# Child.net
KiCad netlist of a schematic drawn in EAGLE
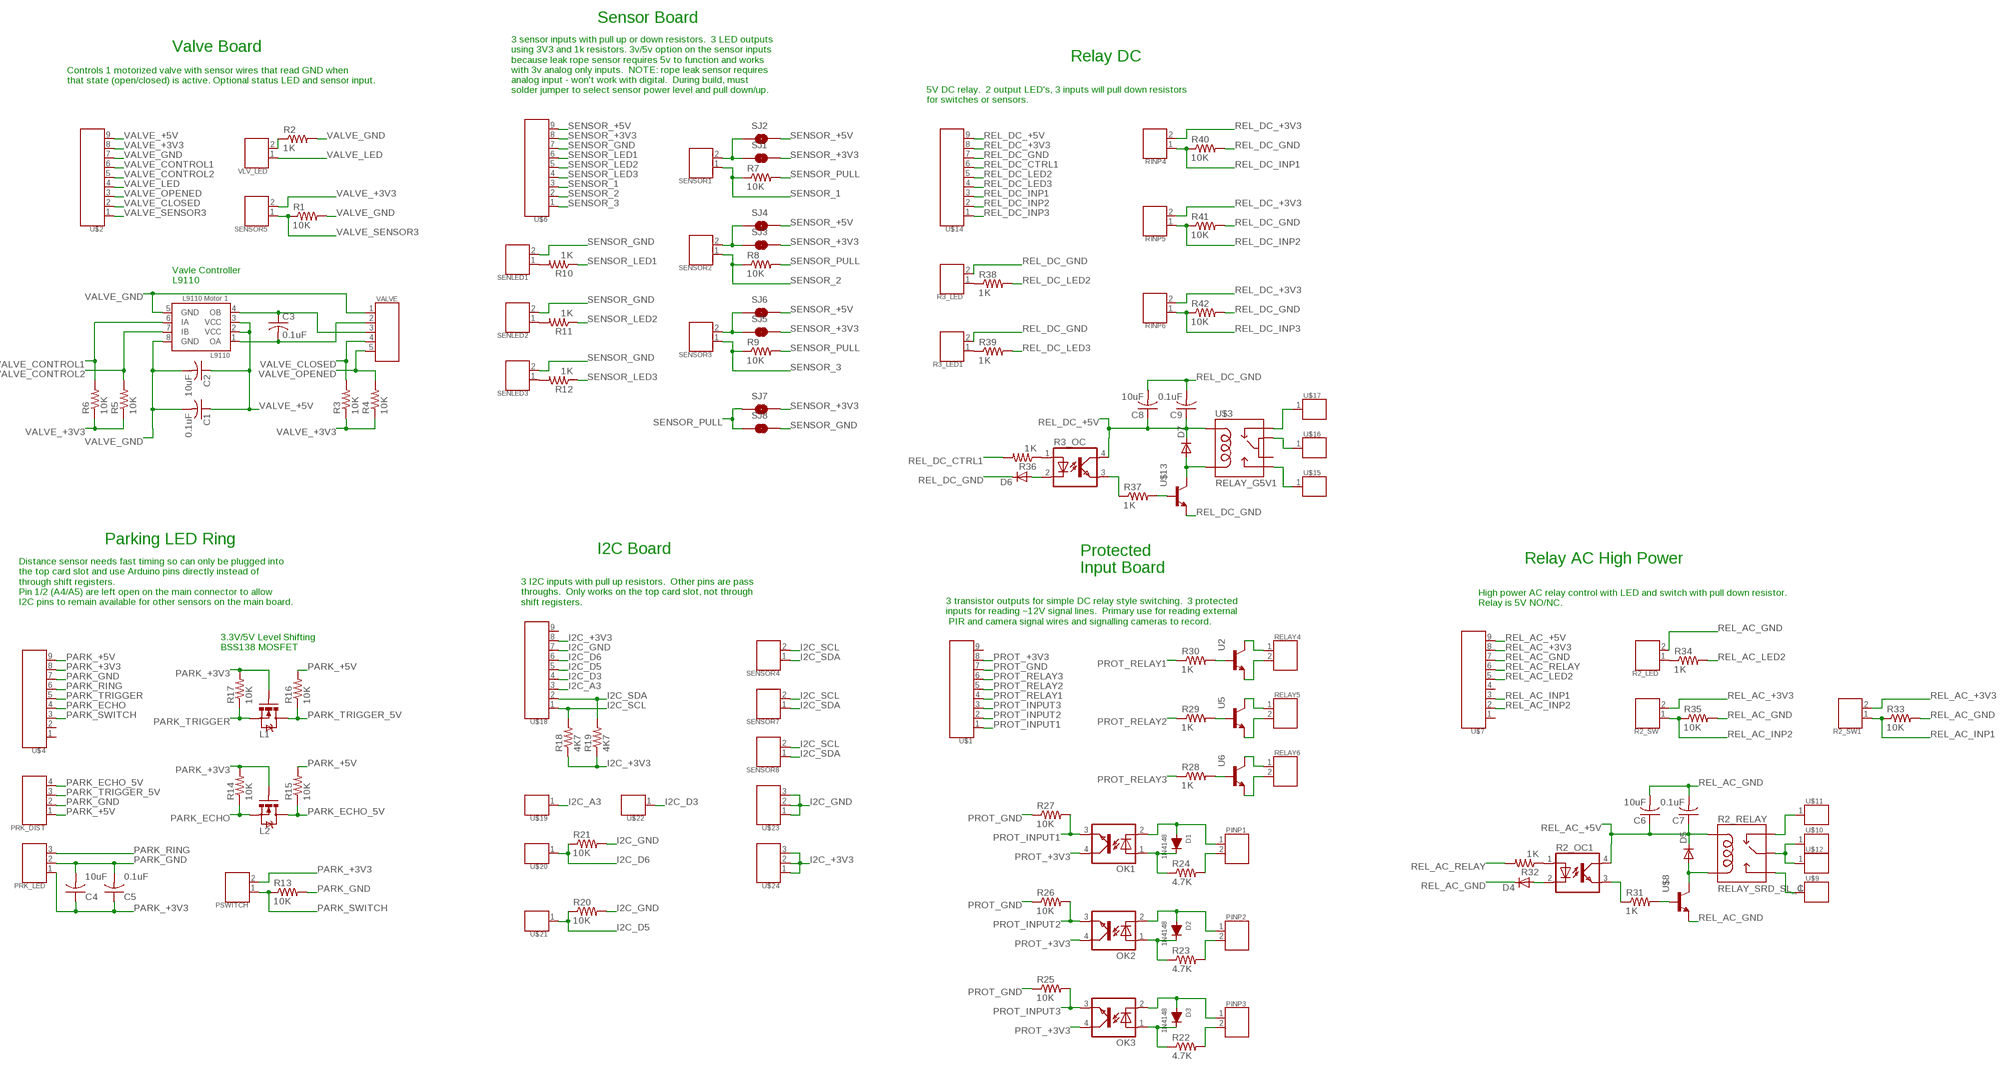
[diagram p0: schematic, sheet 1]

(export (version "E")
  (design (tool "Eeschema 10.0.6"))
  (components
    (comp (ref "C1")
      (value "0.1uF")
      (footprint "eagle-import:CAP_0805")
      (libsource (lib "eagle-import") (part "CAP_0805"))
    )
    (comp (ref "C2")
      (value "10uF")
      (footprint "eagle-import:CAP_0805")
      (libsource (lib "eagle-import") (part "CAP_0805"))
    )
    (comp (ref "C3")
      (value "0.1uF")
      (footprint "eagle-import:CAP_0805")
      (libsource (lib "eagle-import") (part "CAP_0805"))
    )
    (comp (ref "C4")
      (value "10uF")
      (footprint "eagle-import:CAP_0805")
      (libsource (lib "eagle-import") (part "CAP_0805"))
    )
    (comp (ref "C5")
      (value "0.1uF")
      (footprint "eagle-import:CAP_0805")
      (libsource (lib "eagle-import") (part "CAP_0805"))
    )
    (comp (ref "C6")
      (value "10uF")
      (footprint "eagle-import:CAP_0805")
      (libsource (lib "eagle-import") (part "CAP_0805"))
    )
    (comp (ref "C7")
      (value "0.1uF")
      (footprint "eagle-import:CAP_0805")
      (libsource (lib "eagle-import") (part "CAP_0805"))
    )
    (comp (ref "C8")
      (value "10uF")
      (footprint "eagle-import:CAP_0805")
      (libsource (lib "eagle-import") (part "CAP_0805"))
    )
    (comp (ref "C9")
      (value "0.1uF")
      (footprint "eagle-import:CAP_0805")
      (libsource (lib "eagle-import") (part "CAP_0805"))
    )
    (comp (ref "D1")
      (value "1N4148")
      (footprint "eagle-import:SOD123")
      (fields (field (name "MPN") "1N4148W"))
      (libsource (lib "eagle-import") (part "1N4148_SOD123"))
    )
    (comp (ref "D2")
      (value "1N4148")
      (footprint "eagle-import:SOD123")
      (fields (field (name "MPN") "1N4148W"))
      (libsource (lib "eagle-import") (part "1N4148_SOD123"))
    )
    (comp (ref "D3")
      (value "1N4148")
      (footprint "eagle-import:SOD123")
      (fields (field (name "MPN") "1N4148W"))
      (libsource (lib "eagle-import") (part "1N4148_SOD123"))
    )
    (comp (ref "D4")
      (value "DIODESOD323")
      (footprint "eagle-import:SOD323")
      (libsource (lib "eagle-import") (part "DIODESOD323"))
    )
    (comp (ref "D5")
      (value "DIODESOD323")
      (footprint "eagle-import:SOD323")
      (libsource (lib "eagle-import") (part "DIODESOD323"))
    )
    (comp (ref "D6")
      (value "DIODESOD323")
      (footprint "eagle-import:SOD323")
      (libsource (lib "eagle-import") (part "DIODESOD323"))
    )
    (comp (ref "D7")
      (value "DIODESOD323")
      (footprint "eagle-import:SOD323")
      (libsource (lib "eagle-import") (part "DIODESOD323"))
    )
    (comp (ref "L1")
      (value "MOSFET-NCHANNELSMD")
      (footprint "eagle-import:SOT23-3")
      (libsource (lib "eagle-import") (part "MOSFET-NCHANNELSMD"))
    )
    (comp (ref "L2")
      (value "MOSFET-NCHANNELSMD")
      (footprint "eagle-import:SOT23-3")
      (libsource (lib "eagle-import") (part "MOSFET-NCHANNELSMD"))
    )
    (comp (ref "L9110")
      (value "L9110 Motor 1")
      (footprint "eagle-import:SO-08")
      (libsource (lib "eagle-import") (part "IC_L9110_MOTORSO8"))
    )
    (comp (ref "OK1")
      (value "PC817SOP")
      (footprint "eagle-import:SO-4_PC817")
      (libsource (lib "eagle-import") (part "PC817SOP"))
    )
    (comp (ref "OK2")
      (value "PC817SOP")
      (footprint "eagle-import:SO-4_PC817")
      (libsource (lib "eagle-import") (part "PC817SOP"))
    )
    (comp (ref "OK3")
      (value "PC817SOP")
      (footprint "eagle-import:SO-4_PC817")
      (libsource (lib "eagle-import") (part "PC817SOP"))
    )
    (comp (ref "PINP1")
      (value "CONNECTOR_2DUPONT")
      (footprint "eagle-import:DUPONT_2")
      (libsource (lib "eagle-import") (part "CONNECTOR_2DUPONT"))
    )
    (comp (ref "PINP2")
      (value "CONNECTOR_2DUPONT")
      (footprint "eagle-import:DUPONT_2")
      (libsource (lib "eagle-import") (part "CONNECTOR_2DUPONT"))
    )
    (comp (ref "PINP3")
      (value "CONNECTOR_2DUPONT")
      (footprint "eagle-import:DUPONT_2")
      (libsource (lib "eagle-import") (part "CONNECTOR_2DUPONT"))
    )
    (comp (ref "PRK_DIST")
      (value "CONNECTOR_4DUPONT")
      (footprint "eagle-import:DUPONT_4")
      (libsource (lib "eagle-import") (part "CONNECTOR_4DUPONT"))
    )
    (comp (ref "PRK_LED")
      (value "CONNECTOR_3DUPONT")
      (footprint "eagle-import:DUPONT_3")
      (libsource (lib "eagle-import") (part "CONNECTOR_3DUPONT"))
    )
    (comp (ref "PSWITCH")
      (value "CONNECTOR_2DUPONT")
      (footprint "eagle-import:DUPONT_2")
      (libsource (lib "eagle-import") (part "CONNECTOR_2DUPONT"))
    )
    (comp (ref "R1")
      (value "10K")
      (footprint "eagle-import:R_0805")
      (libsource (lib "eagle-import") (part "R_0805"))
    )
    (comp (ref "R2")
      (value "1K")
      (footprint "eagle-import:R_0805")
      (libsource (lib "eagle-import") (part "R_0805"))
    )
    (comp (ref "R2_LED")
      (value "CONNECTOR_2DUPONT")
      (footprint "eagle-import:DUPONT_2")
      (libsource (lib "eagle-import") (part "CONNECTOR_2DUPONT"))
    )
    (comp (ref "R2_OC1")
      (value "PC817SOP")
      (footprint "eagle-import:SO-4_PC817")
      (libsource (lib "eagle-import") (part "PC817SOP"))
    )
    (comp (ref "R2_RELAY")
      (value "RELAY_SRD_SL_C")
      (footprint "eagle-import:RELAY_SRD-SL-C")
      (libsource (lib "eagle-import") (part "RELAY_SRD_SL_C"))
    )
    (comp (ref "R2_SW")
      (value "CONNECTOR_2DUPONT")
      (footprint "eagle-import:DUPONT_2")
      (libsource (lib "eagle-import") (part "CONNECTOR_2DUPONT"))
    )
    (comp (ref "R2_SW1")
      (value "CONNECTOR_2DUPONT")
      (footprint "eagle-import:DUPONT_2")
      (libsource (lib "eagle-import") (part "CONNECTOR_2DUPONT"))
    )
    (comp (ref "R3")
      (value "10K")
      (footprint "eagle-import:R_0805")
      (libsource (lib "eagle-import") (part "R_0805"))
    )
    (comp (ref "R3_LED")
      (value "CONNECTOR_2DUPONT")
      (footprint "eagle-import:DUPONT_2")
      (libsource (lib "eagle-import") (part "CONNECTOR_2DUPONT"))
    )
    (comp (ref "R3_LED1")
      (value "CONNECTOR_2DUPONT")
      (footprint "eagle-import:DUPONT_2")
      (libsource (lib "eagle-import") (part "CONNECTOR_2DUPONT"))
    )
    (comp (ref "R3_OC")
      (value "PC817SOP")
      (footprint "eagle-import:SO-4_PC817")
      (libsource (lib "eagle-import") (part "PC817SOP"))
    )
    (comp (ref "R4")
      (value "10K")
      (footprint "eagle-import:R_0805")
      (libsource (lib "eagle-import") (part "R_0805"))
    )
    (comp (ref "R5")
      (value "10K")
      (footprint "eagle-import:R_0805")
      (libsource (lib "eagle-import") (part "R_0805"))
    )
    (comp (ref "R6")
      (value "10K")
      (footprint "eagle-import:R_0805")
      (libsource (lib "eagle-import") (part "R_0805"))
    )
    (comp (ref "R7")
      (value "10K")
      (footprint "eagle-import:R_0805")
      (libsource (lib "eagle-import") (part "R_0805"))
    )
    (comp (ref "R8")
      (value "10K")
      (footprint "eagle-import:R_0805")
      (libsource (lib "eagle-import") (part "R_0805"))
    )
    (comp (ref "R9")
      (value "10K")
      (footprint "eagle-import:R_0805")
      (libsource (lib "eagle-import") (part "R_0805"))
    )
    (comp (ref "R10")
      (value "1K")
      (footprint "eagle-import:R_0805")
      (libsource (lib "eagle-import") (part "R_0805"))
    )
    (comp (ref "R11")
      (value "1K")
      (footprint "eagle-import:R_0805")
      (libsource (lib "eagle-import") (part "R_0805"))
    )
    (comp (ref "R12")
      (value "1K")
      (footprint "eagle-import:R_0805")
      (libsource (lib "eagle-import") (part "R_0805"))
    )
    (comp (ref "R13")
      (value "10K")
      (footprint "eagle-import:R_0805")
      (libsource (lib "eagle-import") (part "R_0805"))
    )
    (comp (ref "R14")
      (value "10K")
      (footprint "eagle-import:R_0805")
      (libsource (lib "eagle-import") (part "R_0805"))
    )
    (comp (ref "R15")
      (value "10K")
      (footprint "eagle-import:R_0805")
      (libsource (lib "eagle-import") (part "R_0805"))
    )
    (comp (ref "R16")
      (value "10K")
      (footprint "eagle-import:R_0805")
      (libsource (lib "eagle-import") (part "R_0805"))
    )
    (comp (ref "R17")
      (value "10K")
      (footprint "eagle-import:R_0805")
      (libsource (lib "eagle-import") (part "R_0805"))
    )
    (comp (ref "R18")
      (value "4K7")
      (footprint "eagle-import:R_0805")
      (libsource (lib "eagle-import") (part "R_0805"))
    )
    (comp (ref "R19")
      (value "4K7")
      (footprint "eagle-import:R_0805")
      (libsource (lib "eagle-import") (part "R_0805"))
    )
    (comp (ref "R20")
      (value "10K")
      (footprint "eagle-import:R_0805")
      (libsource (lib "eagle-import") (part "R_0805"))
    )
    (comp (ref "R21")
      (value "10K")
      (footprint "eagle-import:R_0805")
      (libsource (lib "eagle-import") (part "R_0805"))
    )
    (comp (ref "R22")
      (value "4.7K")
      (footprint "eagle-import:R_0805")
      (libsource (lib "eagle-import") (part "R_0805"))
    )
    (comp (ref "R23")
      (value "4.7K")
      (footprint "eagle-import:R_0805")
      (libsource (lib "eagle-import") (part "R_0805"))
    )
    (comp (ref "R24")
      (value "4.7K")
      (footprint "eagle-import:R_0805")
      (libsource (lib "eagle-import") (part "R_0805"))
    )
    (comp (ref "R25")
      (value "10K")
      (footprint "eagle-import:R_0805")
      (libsource (lib "eagle-import") (part "R_0805"))
    )
    (comp (ref "R26")
      (value "10K")
      (footprint "eagle-import:R_0805")
      (libsource (lib "eagle-import") (part "R_0805"))
    )
    (comp (ref "R27")
      (value "10K")
      (footprint "eagle-import:R_0805")
      (libsource (lib "eagle-import") (part "R_0805"))
    )
    (comp (ref "R28")
      (value "1K")
      (footprint "eagle-import:R_0805")
      (libsource (lib "eagle-import") (part "R_0805"))
    )
    (comp (ref "R29")
      (value "1K")
      (footprint "eagle-import:R_0805")
      (libsource (lib "eagle-import") (part "R_0805"))
    )
    (comp (ref "R30")
      (value "1K")
      (footprint "eagle-import:R_0805")
      (libsource (lib "eagle-import") (part "R_0805"))
    )
    (comp (ref "R31")
      (value "1K")
      (footprint "eagle-import:R_0805")
      (libsource (lib "eagle-import") (part "R_0805"))
    )
    (comp (ref "R32")
      (value "1K")
      (footprint "eagle-import:R_0805")
      (libsource (lib "eagle-import") (part "R_0805"))
    )
    (comp (ref "R33")
      (value "10K")
      (footprint "eagle-import:R_0805")
      (libsource (lib "eagle-import") (part "R_0805"))
    )
    (comp (ref "R34")
      (value "1K")
      (footprint "eagle-import:R_0805")
      (libsource (lib "eagle-import") (part "R_0805"))
    )
    (comp (ref "R35")
      (value "10K")
      (footprint "eagle-import:R_0805")
      (libsource (lib "eagle-import") (part "R_0805"))
    )
    (comp (ref "R36")
      (value "1K")
      (footprint "eagle-import:R_0805")
      (libsource (lib "eagle-import") (part "R_0805"))
    )
    (comp (ref "R37")
      (value "1K")
      (footprint "eagle-import:R_0805")
      (libsource (lib "eagle-import") (part "R_0805"))
    )
    (comp (ref "R38")
      (value "1K")
      (footprint "eagle-import:R_0805")
      (libsource (lib "eagle-import") (part "R_0805"))
    )
    (comp (ref "R39")
      (value "1K")
      (footprint "eagle-import:R_0805")
      (libsource (lib "eagle-import") (part "R_0805"))
    )
    (comp (ref "R40")
      (value "10K")
      (footprint "eagle-import:R_0805")
      (libsource (lib "eagle-import") (part "R_0805"))
    )
    (comp (ref "R41")
      (value "10K")
      (footprint "eagle-import:R_0805")
      (libsource (lib "eagle-import") (part "R_0805"))
    )
    (comp (ref "R42")
      (value "10K")
      (footprint "eagle-import:R_0805")
      (libsource (lib "eagle-import") (part "R_0805"))
    )
    (comp (ref "RELAY4")
      (value "CONNECTOR_2DUPONT")
      (footprint "eagle-import:DUPONT_2")
      (libsource (lib "eagle-import") (part "CONNECTOR_2DUPONT"))
    )
    (comp (ref "RELAY5")
      (value "CONNECTOR_2DUPONT")
      (footprint "eagle-import:DUPONT_2")
      (libsource (lib "eagle-import") (part "CONNECTOR_2DUPONT"))
    )
    (comp (ref "RELAY6")
      (value "CONNECTOR_2DUPONT")
      (footprint "eagle-import:DUPONT_2")
      (libsource (lib "eagle-import") (part "CONNECTOR_2DUPONT"))
    )
    (comp (ref "RINP4")
      (value "CONNECTOR_2DUPONT")
      (footprint "eagle-import:DUPONT_2")
      (libsource (lib "eagle-import") (part "CONNECTOR_2DUPONT"))
    )
    (comp (ref "RINP5")
      (value "CONNECTOR_2DUPONT")
      (footprint "eagle-import:DUPONT_2")
      (libsource (lib "eagle-import") (part "CONNECTOR_2DUPONT"))
    )
    (comp (ref "RINP6")
      (value "CONNECTOR_2DUPONT")
      (footprint "eagle-import:DUPONT_2")
      (libsource (lib "eagle-import") (part "CONNECTOR_2DUPONT"))
    )
    (comp (ref "SENLED1")
      (value "CONNECTOR_2DUPONT")
      (footprint "eagle-import:DUPONT_2")
      (libsource (lib "eagle-import") (part "CONNECTOR_2DUPONT"))
    )
    (comp (ref "SENLED2")
      (value "CONNECTOR_2DUPONT")
      (footprint "eagle-import:DUPONT_2")
      (libsource (lib "eagle-import") (part "CONNECTOR_2DUPONT"))
    )
    (comp (ref "SENLED3")
      (value "CONNECTOR_2DUPONT")
      (footprint "eagle-import:DUPONT_2")
      (libsource (lib "eagle-import") (part "CONNECTOR_2DUPONT"))
    )
    (comp (ref "SENSOR1")
      (value "CONNECTOR_2DUPONT")
      (footprint "eagle-import:DUPONT_2")
      (libsource (lib "eagle-import") (part "CONNECTOR_2DUPONT"))
    )
    (comp (ref "SENSOR2")
      (value "CONNECTOR_2DUPONT")
      (footprint "eagle-import:DUPONT_2")
      (libsource (lib "eagle-import") (part "CONNECTOR_2DUPONT"))
    )
    (comp (ref "SENSOR3")
      (value "CONNECTOR_2DUPONT")
      (footprint "eagle-import:DUPONT_2")
      (libsource (lib "eagle-import") (part "CONNECTOR_2DUPONT"))
    )
    (comp (ref "SENSOR4")
      (value "CONNECTOR_2DUPONT")
      (footprint "eagle-import:DUPONT_2")
      (libsource (lib "eagle-import") (part "CONNECTOR_2DUPONT"))
    )
    (comp (ref "SENSOR5")
      (value "CONNECTOR_2DUPONT")
      (footprint "eagle-import:DUPONT_2")
      (libsource (lib "eagle-import") (part "CONNECTOR_2DUPONT"))
    )
    (comp (ref "SENSOR7")
      (value "CONNECTOR_2DUPONT")
      (footprint "eagle-import:DUPONT_2")
      (libsource (lib "eagle-import") (part "CONNECTOR_2DUPONT"))
    )
    (comp (ref "SENSOR8")
      (value "CONNECTOR_2DUPONT")
      (footprint "eagle-import:DUPONT_2")
      (libsource (lib "eagle-import") (part "CONNECTOR_2DUPONT"))
    )
    (comp (ref "SJ1")
      (value "JUMPER-PAD-2-NOYES_SILK")
      (footprint "eagle-import:PAD-JUMPER-2-NO_YES_SILK")
      (libsource (lib "eagle-import") (part "JUMPER-PAD-2-NOYES_SILK"))
    )
    (comp (ref "SJ2")
      (value "JUMPER-PAD-2-NOYES_SILK")
      (footprint "eagle-import:PAD-JUMPER-2-NO_YES_SILK")
      (libsource (lib "eagle-import") (part "JUMPER-PAD-2-NOYES_SILK"))
    )
    (comp (ref "SJ3")
      (value "JUMPER-PAD-2-NOYES_SILK")
      (footprint "eagle-import:PAD-JUMPER-2-NO_YES_SILK")
      (libsource (lib "eagle-import") (part "JUMPER-PAD-2-NOYES_SILK"))
    )
    (comp (ref "SJ4")
      (value "JUMPER-PAD-2-NOYES_SILK")
      (footprint "eagle-import:PAD-JUMPER-2-NO_YES_SILK")
      (libsource (lib "eagle-import") (part "JUMPER-PAD-2-NOYES_SILK"))
    )
    (comp (ref "SJ5")
      (value "JUMPER-PAD-2-NOYES_SILK")
      (footprint "eagle-import:PAD-JUMPER-2-NO_YES_SILK")
      (libsource (lib "eagle-import") (part "JUMPER-PAD-2-NOYES_SILK"))
    )
    (comp (ref "SJ6")
      (value "JUMPER-PAD-2-NOYES_SILK")
      (footprint "eagle-import:PAD-JUMPER-2-NO_YES_SILK")
      (libsource (lib "eagle-import") (part "JUMPER-PAD-2-NOYES_SILK"))
    )
    (comp (ref "SJ7")
      (value "JUMPER-PAD-2-NOYES_SILK")
      (footprint "eagle-import:PAD-JUMPER-2-NO_YES_SILK")
      (libsource (lib "eagle-import") (part "JUMPER-PAD-2-NOYES_SILK"))
    )
    (comp (ref "SJ8")
      (value "JUMPER-PAD-2-NOYES_SILK")
      (footprint "eagle-import:PAD-JUMPER-2-NO_YES_SILK")
      (libsource (lib "eagle-import") (part "JUMPER-PAD-2-NOYES_SILK"))
    )
    (comp (ref "U$1")
      (value "CONNECTOR_9DUP_FEM90")
      (footprint "eagle-import:DUPONT_FEM90_9")
      (libsource (lib "eagle-import") (part "CONNECTOR_9DUP_FEM90"))
    )
    (comp (ref "U$2")
      (value "CONNECTOR_9DUP_FEM90")
      (footprint "eagle-import:DUPONT_FEM90_9")
      (libsource (lib "eagle-import") (part "CONNECTOR_9DUP_FEM90"))
    )
    (comp (ref "U$3")
      (value "RELAY_G5V1")
      (footprint "eagle-import:RELAY-G5V")
      (libsource (lib "eagle-import") (part "RELAY_G5V1"))
    )
    (comp (ref "U$4")
      (value "CONNECTOR_9DUPONT")
      (footprint "eagle-import:DUPONT_9")
      (libsource (lib "eagle-import") (part "CONNECTOR_9DUPONT"))
    )
    (comp (ref "U$6")
      (value "CONNECTOR_9DUP_FEM90")
      (footprint "eagle-import:DUPONT_FEM90_9")
      (libsource (lib "eagle-import") (part "CONNECTOR_9DUP_FEM90"))
    )
    (comp (ref "U$7")
      (value "CONNECTOR_9DUP_FEM90")
      (footprint "eagle-import:DUPONT_FEM90_9")
      (libsource (lib "eagle-import") (part "CONNECTOR_9DUP_FEM90"))
    )
    (comp (ref "U$8")
      (value "TRANSISTORSMD")
      (footprint "eagle-import:SOT23-3")
      (libsource (lib "eagle-import") (part "TRANSISTORSMD"))
    )
    (comp (ref "U$9")
      (value "CONNECTOR_1DUP_LARGE")
      (footprint "eagle-import:DUPONT_1_LRG")
      (libsource (lib "eagle-import") (part "CONNECTOR_1DUP_LARGE"))
    )
    (comp (ref "U$10")
      (value "CONNECTOR_1DUP_LARGE")
      (footprint "eagle-import:DUPONT_1_LRG")
      (libsource (lib "eagle-import") (part "CONNECTOR_1DUP_LARGE"))
    )
    (comp (ref "U$11")
      (value "CONNECTOR_1DUP_LARGE")
      (footprint "eagle-import:DUPONT_1_LRG")
      (libsource (lib "eagle-import") (part "CONNECTOR_1DUP_LARGE"))
    )
    (comp (ref "U$12")
      (value "CONNECTOR_1DUP_LARGE")
      (footprint "eagle-import:DUPONT_1_LRG")
      (libsource (lib "eagle-import") (part "CONNECTOR_1DUP_LARGE"))
    )
    (comp (ref "U$13")
      (value "TRANSISTORSMD")
      (footprint "eagle-import:SOT23-3")
      (libsource (lib "eagle-import") (part "TRANSISTORSMD"))
    )
    (comp (ref "U$14")
      (value "CONNECTOR_9DUP_FEM90")
      (footprint "eagle-import:DUPONT_FEM90_9")
      (libsource (lib "eagle-import") (part "CONNECTOR_9DUP_FEM90"))
    )
    (comp (ref "U$15")
      (value "CONNECTOR_1DUPONT")
      (footprint "eagle-import:DUPONT_1")
      (libsource (lib "eagle-import") (part "CONNECTOR_1DUPONT"))
    )
    (comp (ref "U$16")
      (value "CONNECTOR_1DUPONT")
      (footprint "eagle-import:DUPONT_1")
      (libsource (lib "eagle-import") (part "CONNECTOR_1DUPONT"))
    )
    (comp (ref "U$17")
      (value "CONNECTOR_1DUPONT")
      (footprint "eagle-import:DUPONT_1")
      (libsource (lib "eagle-import") (part "CONNECTOR_1DUPONT"))
    )
    (comp (ref "U$18")
      (value "CONNECTOR_9DUP_FEM90")
      (footprint "eagle-import:DUPONT_FEM90_9")
      (libsource (lib "eagle-import") (part "CONNECTOR_9DUP_FEM90"))
    )
    (comp (ref "U$19")
      (value "CONNECTOR_1DUPONT")
      (footprint "eagle-import:DUPONT_1")
      (libsource (lib "eagle-import") (part "CONNECTOR_1DUPONT"))
    )
    (comp (ref "U$20")
      (value "CONNECTOR_1DUPONT")
      (footprint "eagle-import:DUPONT_1")
      (libsource (lib "eagle-import") (part "CONNECTOR_1DUPONT"))
    )
    (comp (ref "U$21")
      (value "CONNECTOR_1DUPONT")
      (footprint "eagle-import:DUPONT_1")
      (libsource (lib "eagle-import") (part "CONNECTOR_1DUPONT"))
    )
    (comp (ref "U$22")
      (value "CONNECTOR_1DUPONT")
      (footprint "eagle-import:DUPONT_1")
      (libsource (lib "eagle-import") (part "CONNECTOR_1DUPONT"))
    )
    (comp (ref "U$23")
      (value "CONNECTOR_3DUPONT")
      (footprint "eagle-import:DUPONT_3")
      (libsource (lib "eagle-import") (part "CONNECTOR_3DUPONT"))
    )
    (comp (ref "U$24")
      (value "CONNECTOR_3DUPONT")
      (footprint "eagle-import:DUPONT_3")
      (libsource (lib "eagle-import") (part "CONNECTOR_3DUPONT"))
    )
    (comp (ref "U2")
      (value "TRANSISTORSMD")
      (footprint "eagle-import:SOT23-3")
      (libsource (lib "eagle-import") (part "TRANSISTORSMD"))
    )
    (comp (ref "U5")
      (value "TRANSISTORSMD")
      (footprint "eagle-import:SOT23-3")
      (libsource (lib "eagle-import") (part "TRANSISTORSMD"))
    )
    (comp (ref "U6")
      (value "TRANSISTORSMD")
      (footprint "eagle-import:SOT23-3")
      (libsource (lib "eagle-import") (part "TRANSISTORSMD"))
    )
    (comp (ref "VALVE")
      (value "CONNECTOR_5DUPONT")
      (footprint "eagle-import:DUPONT_5")
      (libsource (lib "eagle-import") (part "CONNECTOR_5DUPONT"))
    )
    (comp (ref "VLV_LED")
      (value "CONNECTOR_2DUPONT")
      (footprint "eagle-import:DUPONT_2")
      (libsource (lib "eagle-import") (part "CONNECTOR_2DUPONT"))
    )
  )
  (nets
    (net (code "1") (name "/I2C_+3V3") (class "Default")
      (node (ref "R18") (pin "1") (pinfunction "1_1") (pintype "passive"))
      (node (ref "R19") (pin "1") (pinfunction "1_1") (pintype "passive"))
      (node (ref "U$18") (pin "8") (pinfunction "8_8") (pintype "bidirectional"))
      (node (ref "U$24") (pin "1") (pinfunction "1_1") (pintype "bidirectional"))
      (node (ref "U$24") (pin "2") (pinfunction "2_2") (pintype "bidirectional"))
      (node (ref "U$24") (pin "3") (pinfunction "3_3") (pintype "bidirectional"))
    )
    (net (code "2") (name "/I2C_A3") (class "Default")
      (node (ref "U$18") (pin "3") (pinfunction "3_3") (pintype "bidirectional"))
      (node (ref "U$19") (pin "1") (pinfunction "1_1") (pintype "bidirectional"))
    )
    (net (code "3") (name "/I2C_D3") (class "Default")
      (node (ref "U$18") (pin "4") (pinfunction "4_4") (pintype "bidirectional"))
      (node (ref "U$22") (pin "1") (pinfunction "1_1") (pintype "bidirectional"))
    )
    (net (code "4") (name "/I2C_D5") (class "Default")
      (node (ref "R20") (pin "1") (pinfunction "1_1") (pintype "passive"))
      (node (ref "U$18") (pin "5") (pinfunction "5_5") (pintype "bidirectional"))
      (node (ref "U$21") (pin "1") (pinfunction "1_1") (pintype "bidirectional"))
    )
    (net (code "5") (name "/I2C_D6") (class "Default")
      (node (ref "R21") (pin "1") (pinfunction "1_1") (pintype "passive"))
      (node (ref "U$18") (pin "6") (pinfunction "6_6") (pintype "bidirectional"))
      (node (ref "U$20") (pin "1") (pinfunction "1_1") (pintype "bidirectional"))
    )
    (net (code "6") (name "/I2C_GND") (class "Default")
      (node (ref "R20") (pin "2") (pinfunction "2_2") (pintype "passive"))
      (node (ref "R21") (pin "2") (pinfunction "2_2") (pintype "passive"))
      (node (ref "U$18") (pin "7") (pinfunction "7_7") (pintype "bidirectional"))
      (node (ref "U$23") (pin "1") (pinfunction "1_1") (pintype "bidirectional"))
      (node (ref "U$23") (pin "2") (pinfunction "2_2") (pintype "bidirectional"))
      (node (ref "U$23") (pin "3") (pinfunction "3_3") (pintype "bidirectional"))
    )
    (net (code "7") (name "/I2C_SCL") (class "Default")
      (node (ref "R18") (pin "2") (pinfunction "2_2") (pintype "passive"))
      (node (ref "SENSOR4") (pin "2") (pinfunction "2_2") (pintype "bidirectional"))
      (node (ref "SENSOR7") (pin "2") (pinfunction "2_2") (pintype "bidirectional"))
      (node (ref "SENSOR8") (pin "2") (pinfunction "2_2") (pintype "bidirectional"))
      (node (ref "U$18") (pin "1") (pinfunction "1_1") (pintype "bidirectional"))
    )
    (net (code "8") (name "/I2C_SDA") (class "Default")
      (node (ref "R19") (pin "2") (pinfunction "2_2") (pintype "passive"))
      (node (ref "SENSOR4") (pin "1") (pinfunction "1_1") (pintype "bidirectional"))
      (node (ref "SENSOR7") (pin "1") (pinfunction "1_1") (pintype "bidirectional"))
      (node (ref "SENSOR8") (pin "1") (pinfunction "1_1") (pintype "bidirectional"))
      (node (ref "U$18") (pin "2") (pinfunction "2_2") (pintype "bidirectional"))
    )
    (net (code "9") (name "/PARK_+3V3") (class "Default")
      (node (ref "C4") (pin "1") (pinfunction "1_1") (pintype "passive"))
      (node (ref "C5") (pin "1") (pinfunction "1_1") (pintype "passive"))
      (node (ref "L1") (pin "1") (pinfunction "G_1") (pintype "passive"))
      (node (ref "L2") (pin "1") (pinfunction "G_1") (pintype "passive"))
      (node (ref "PRK_LED") (pin "1") (pinfunction "1_1") (pintype "bidirectional"))
      (node (ref "PSWITCH") (pin "2") (pinfunction "2_2") (pintype "bidirectional"))
      (node (ref "R14") (pin "2") (pinfunction "2_2") (pintype "passive"))
      (node (ref "R17") (pin "2") (pinfunction "2_2") (pintype "passive"))
      (node (ref "U$4") (pin "8") (pinfunction "8_8") (pintype "bidirectional"))
    )
    (net (code "10") (name "/PARK_+5V") (class "Default")
      (node (ref "PRK_DIST") (pin "1") (pinfunction "1_1") (pintype "bidirectional"))
      (node (ref "R15") (pin "2") (pinfunction "2_2") (pintype "passive"))
      (node (ref "R16") (pin "2") (pinfunction "2_2") (pintype "passive"))
      (node (ref "U$4") (pin "9") (pinfunction "9_9") (pintype "bidirectional"))
    )
    (net (code "11") (name "/PARK_ECHO") (class "Default")
      (node (ref "L2") (pin "2") (pinfunction "S_2") (pintype "passive"))
      (node (ref "R14") (pin "1") (pinfunction "1_1") (pintype "passive"))
      (node (ref "U$4") (pin "4") (pinfunction "4_4") (pintype "bidirectional"))
    )
    (net (code "12") (name "/PARK_ECHO_5V") (class "Default")
      (node (ref "L2") (pin "3") (pinfunction "D_3") (pintype "passive"))
      (node (ref "PRK_DIST") (pin "4") (pinfunction "4_4") (pintype "bidirectional"))
      (node (ref "R15") (pin "1") (pinfunction "1_1") (pintype "passive"))
    )
    (net (code "13") (name "/PARK_GND") (class "Default")
      (node (ref "C4") (pin "2") (pinfunction "2_2") (pintype "passive"))
      (node (ref "C5") (pin "2") (pinfunction "2_2") (pintype "passive"))
      (node (ref "PRK_DIST") (pin "2") (pinfunction "2_2") (pintype "bidirectional"))
      (node (ref "PRK_LED") (pin "2") (pinfunction "2_2") (pintype "bidirectional"))
      (node (ref "R13") (pin "2") (pinfunction "2_2") (pintype "passive"))
      (node (ref "U$4") (pin "7") (pinfunction "7_7") (pintype "bidirectional"))
    )
    (net (code "14") (name "/PARK_RING") (class "Default")
      (node (ref "PRK_LED") (pin "3") (pinfunction "3_3") (pintype "bidirectional"))
      (node (ref "U$4") (pin "6") (pinfunction "6_6") (pintype "bidirectional"))
    )
    (net (code "15") (name "/PARK_SWITCH") (class "Default")
      (node (ref "PSWITCH") (pin "1") (pinfunction "1_1") (pintype "bidirectional"))
      (node (ref "R13") (pin "1") (pinfunction "1_1") (pintype "passive"))
      (node (ref "U$4") (pin "3") (pinfunction "3_3") (pintype "bidirectional"))
    )
    (net (code "16") (name "/PARK_TRIGGER") (class "Default")
      (node (ref "L1") (pin "2") (pinfunction "S_2") (pintype "passive"))
      (node (ref "R17") (pin "1") (pinfunction "1_1") (pintype "passive"))
      (node (ref "U$4") (pin "5") (pinfunction "5_5") (pintype "bidirectional"))
    )
    (net (code "17") (name "/PARK_TRIGGER_5V") (class "Default")
      (node (ref "L1") (pin "3") (pinfunction "D_3") (pintype "passive"))
      (node (ref "PRK_DIST") (pin "3") (pinfunction "3_3") (pintype "bidirectional"))
      (node (ref "R16") (pin "1") (pinfunction "1_1") (pintype "passive"))
    )
    (net (code "18") (name "/PROT_+3V3") (class "Default")
      (node (ref "OK1") (pin "4") (pinfunction "COL_4") (pintype "passive"))
      (node (ref "OK2") (pin "4") (pinfunction "COL_4") (pintype "passive"))
      (node (ref "OK3") (pin "4") (pinfunction "COL_4") (pintype "passive"))
      (node (ref "U$1") (pin "8") (pinfunction "8_8") (pintype "bidirectional"))
    )
    (net (code "19") (name "/PROT_GND") (class "Default")
      (node (ref "R25") (pin "1") (pinfunction "1_1") (pintype "passive"))
      (node (ref "R26") (pin "1") (pinfunction "1_1") (pintype "passive"))
      (node (ref "R27") (pin "1") (pinfunction "1_1") (pintype "passive"))
      (node (ref "U$1") (pin "7") (pinfunction "7_7") (pintype "bidirectional"))
    )
    (net (code "20") (name "/PROT_INPUT1") (class "Default")
      (node (ref "OK1") (pin "3") (pinfunction "EMIT_3") (pintype "passive"))
      (node (ref "R27") (pin "2") (pinfunction "2_2") (pintype "passive"))
      (node (ref "U$1") (pin "1") (pinfunction "1_1") (pintype "bidirectional"))
    )
    (net (code "21") (name "/PROT_INPUT2") (class "Default")
      (node (ref "OK2") (pin "3") (pinfunction "EMIT_3") (pintype "passive"))
      (node (ref "R26") (pin "2") (pinfunction "2_2") (pintype "passive"))
      (node (ref "U$1") (pin "2") (pinfunction "2_2") (pintype "bidirectional"))
    )
    (net (code "22") (name "/PROT_INPUT3") (class "Default")
      (node (ref "OK3") (pin "3") (pinfunction "EMIT_3") (pintype "passive"))
      (node (ref "R25") (pin "2") (pinfunction "2_2") (pintype "passive"))
      (node (ref "U$1") (pin "3") (pinfunction "3_3") (pintype "bidirectional"))
    )
    (net (code "23") (name "/PROT_RELAY1") (class "Default")
      (node (ref "R30") (pin "1") (pinfunction "1_1") (pintype "passive"))
      (node (ref "U$1") (pin "4") (pinfunction "4_4") (pintype "bidirectional"))
    )
    (net (code "24") (name "/PROT_RELAY2") (class "Default")
      (node (ref "R29") (pin "1") (pinfunction "1_1") (pintype "passive"))
      (node (ref "U$1") (pin "5") (pinfunction "5_5") (pintype "bidirectional"))
    )
    (net (code "25") (name "/PROT_RELAY3") (class "Default")
      (node (ref "R28") (pin "1") (pinfunction "1_1") (pintype "passive"))
      (node (ref "U$1") (pin "6") (pinfunction "6_6") (pintype "bidirectional"))
    )
    (net (code "26") (name "/REL_AC_+3V3") (class "Default")
      (node (ref "R2_SW") (pin "2") (pinfunction "2_2") (pintype "bidirectional"))
      (node (ref "R2_SW1") (pin "2") (pinfunction "2_2") (pintype "bidirectional"))
      (node (ref "U$7") (pin "8") (pinfunction "8_8") (pintype "bidirectional"))
    )
    (net (code "27") (name "/REL_AC_+5V") (class "Default")
      (node (ref "C6") (pin "1") (pinfunction "1_1") (pintype "passive"))
      (node (ref "C7") (pin "1") (pinfunction "1_1") (pintype "passive"))
      (node (ref "D5") (pin "C") (pinfunction "C_C") (pintype "passive"))
      (node (ref "R2_OC1") (pin "4") (pinfunction "COL_4") (pintype "passive"))
      (node (ref "R2_RELAY") (pin "1") (pinfunction "COIL_A_1") (pintype "bidirectional"))
      (node (ref "U$7") (pin "9") (pinfunction "9_9") (pintype "bidirectional"))
    )
    (net (code "28") (name "/REL_AC_GND") (class "Default")
      (node (ref "C6") (pin "2") (pinfunction "2_2") (pintype "passive"))
      (node (ref "C7") (pin "2") (pinfunction "2_2") (pintype "passive"))
      (node (ref "D4") (pin "C") (pinfunction "C_C") (pintype "passive"))
      (node (ref "R2_LED") (pin "2") (pinfunction "2_2") (pintype "bidirectional"))
      (node (ref "R33") (pin "2") (pinfunction "2_2") (pintype "passive"))
      (node (ref "R35") (pin "2") (pinfunction "2_2") (pintype "passive"))
      (node (ref "U$7") (pin "7") (pinfunction "7_7") (pintype "bidirectional"))
      (node (ref "U$8") (pin "2") (pinfunction "EMITTER_2") (pintype "passive"))
    )
    (net (code "29") (name "/REL_AC_INP1") (class "Default")
      (node (ref "R2_SW1") (pin "1") (pinfunction "1_1") (pintype "bidirectional"))
      (node (ref "R33") (pin "1") (pinfunction "1_1") (pintype "passive"))
      (node (ref "U$7") (pin "3") (pinfunction "3_3") (pintype "bidirectional"))
    )
    (net (code "30") (name "/REL_AC_INP2") (class "Default")
      (node (ref "R2_SW") (pin "1") (pinfunction "1_1") (pintype "bidirectional"))
      (node (ref "R35") (pin "1") (pinfunction "1_1") (pintype "passive"))
      (node (ref "U$7") (pin "2") (pinfunction "2_2") (pintype "bidirectional"))
    )
    (net (code "31") (name "/REL_AC_LED2") (class "Default")
      (node (ref "R34") (pin "2") (pinfunction "2_2") (pintype "passive"))
      (node (ref "U$7") (pin "5") (pinfunction "5_5") (pintype "bidirectional"))
    )
    (net (code "32") (name "/REL_AC_RELAY") (class "Default")
      (node (ref "R32") (pin "2") (pinfunction "2_2") (pintype "passive"))
      (node (ref "U$7") (pin "6") (pinfunction "6_6") (pintype "bidirectional"))
    )
    (net (code "33") (name "/REL_DC_+3V3") (class "Default")
      (node (ref "RINP4") (pin "2") (pinfunction "2_2") (pintype "bidirectional"))
      (node (ref "RINP5") (pin "2") (pinfunction "2_2") (pintype "bidirectional"))
      (node (ref "RINP6") (pin "2") (pinfunction "2_2") (pintype "bidirectional"))
      (node (ref "U$14") (pin "8") (pinfunction "8_8") (pintype "bidirectional"))
    )
    (net (code "34") (name "/REL_DC_+5V") (class "Default")
      (node (ref "C8") (pin "1") (pinfunction "1_1") (pintype "passive"))
      (node (ref "C9") (pin "1") (pinfunction "1_1") (pintype "passive"))
      (node (ref "D7") (pin "C") (pinfunction "C_C") (pintype "passive"))
      (node (ref "R3_OC") (pin "4") (pinfunction "COL_4") (pintype "passive"))
      (node (ref "U$14") (pin "9") (pinfunction "9_9") (pintype "bidirectional"))
      (node (ref "U$3") (pin "2") (pinfunction "2_2") (pintype "bidirectional"))
    )
    (net (code "35") (name "/REL_DC_CTRL1") (class "Default")
      (node (ref "R36") (pin "2") (pinfunction "2_2") (pintype "passive"))
      (node (ref "U$14") (pin "6") (pinfunction "6_6") (pintype "bidirectional"))
    )
    (net (code "36") (name "/REL_DC_GND") (class "Default")
      (node (ref "C8") (pin "2") (pinfunction "2_2") (pintype "passive"))
      (node (ref "C9") (pin "2") (pinfunction "2_2") (pintype "passive"))
      (node (ref "D6") (pin "C") (pinfunction "C_C") (pintype "passive"))
      (node (ref "R3_LED") (pin "2") (pinfunction "2_2") (pintype "bidirectional"))
      (node (ref "R3_LED1") (pin "2") (pinfunction "2_2") (pintype "bidirectional"))
      (node (ref "R40") (pin "2") (pinfunction "2_2") (pintype "passive"))
      (node (ref "R41") (pin "2") (pinfunction "2_2") (pintype "passive"))
      (node (ref "R42") (pin "2") (pinfunction "2_2") (pintype "passive"))
      (node (ref "U$13") (pin "2") (pinfunction "EMITTER_2") (pintype "passive"))
      (node (ref "U$14") (pin "7") (pinfunction "7_7") (pintype "bidirectional"))
    )
    (net (code "37") (name "/REL_DC_INP1") (class "Default")
      (node (ref "R40") (pin "1") (pinfunction "1_1") (pintype "passive"))
      (node (ref "RINP4") (pin "1") (pinfunction "1_1") (pintype "bidirectional"))
      (node (ref "U$14") (pin "3") (pinfunction "3_3") (pintype "bidirectional"))
    )
    (net (code "38") (name "/REL_DC_INP2") (class "Default")
      (node (ref "R41") (pin "1") (pinfunction "1_1") (pintype "passive"))
      (node (ref "RINP5") (pin "1") (pinfunction "1_1") (pintype "bidirectional"))
      (node (ref "U$14") (pin "2") (pinfunction "2_2") (pintype "bidirectional"))
    )
    (net (code "39") (name "/REL_DC_INP3") (class "Default")
      (node (ref "R42") (pin "1") (pinfunction "1_1") (pintype "passive"))
      (node (ref "RINP6") (pin "1") (pinfunction "1_1") (pintype "bidirectional"))
      (node (ref "U$14") (pin "1") (pinfunction "1_1") (pintype "bidirectional"))
    )
    (net (code "40") (name "/REL_DC_LED2") (class "Default")
      (node (ref "R38") (pin "2") (pinfunction "2_2") (pintype "passive"))
      (node (ref "U$14") (pin "5") (pinfunction "5_5") (pintype "bidirectional"))
    )
    (net (code "41") (name "/REL_DC_LED3") (class "Default")
      (node (ref "R39") (pin "2") (pinfunction "2_2") (pintype "passive"))
      (node (ref "U$14") (pin "4") (pinfunction "4_4") (pintype "bidirectional"))
    )
    (net (code "42") (name "/SENSOR_+3V3") (class "Default")
      (node (ref "SJ1") (pin "2") (pinfunction "2_2") (pintype "passive"))
      (node (ref "SJ3") (pin "2") (pinfunction "2_2") (pintype "passive"))
      (node (ref "SJ5") (pin "2") (pinfunction "2_2") (pintype "passive"))
      (node (ref "SJ7") (pin "2") (pinfunction "2_2") (pintype "passive"))
      (node (ref "U$6") (pin "8") (pinfunction "8_8") (pintype "bidirectional"))
    )
    (net (code "43") (name "/SENSOR_+5V") (class "Default")
      (node (ref "SJ2") (pin "2") (pinfunction "2_2") (pintype "passive"))
      (node (ref "SJ4") (pin "2") (pinfunction "2_2") (pintype "passive"))
      (node (ref "SJ6") (pin "2") (pinfunction "2_2") (pintype "passive"))
      (node (ref "U$6") (pin "9") (pinfunction "9_9") (pintype "bidirectional"))
    )
    (net (code "44") (name "/SENSOR_1") (class "Default")
      (node (ref "R7") (pin "1") (pinfunction "1_1") (pintype "passive"))
      (node (ref "SENSOR1") (pin "1") (pinfunction "1_1") (pintype "bidirectional"))
      (node (ref "U$6") (pin "3") (pinfunction "3_3") (pintype "bidirectional"))
    )
    (net (code "45") (name "/SENSOR_2") (class "Default")
      (node (ref "R8") (pin "1") (pinfunction "1_1") (pintype "passive"))
      (node (ref "SENSOR2") (pin "1") (pinfunction "1_1") (pintype "bidirectional"))
      (node (ref "U$6") (pin "2") (pinfunction "2_2") (pintype "bidirectional"))
    )
    (net (code "46") (name "/SENSOR_3") (class "Default")
      (node (ref "R9") (pin "1") (pinfunction "1_1") (pintype "passive"))
      (node (ref "SENSOR3") (pin "1") (pinfunction "1_1") (pintype "bidirectional"))
      (node (ref "U$6") (pin "1") (pinfunction "1_1") (pintype "bidirectional"))
    )
    (net (code "47") (name "/SENSOR_GND") (class "Default")
      (node (ref "SENLED1") (pin "2") (pinfunction "2_2") (pintype "bidirectional"))
      (node (ref "SENLED2") (pin "2") (pinfunction "2_2") (pintype "bidirectional"))
      (node (ref "SENLED3") (pin "2") (pinfunction "2_2") (pintype "bidirectional"))
      (node (ref "SJ8") (pin "2") (pinfunction "2_2") (pintype "passive"))
      (node (ref "U$6") (pin "7") (pinfunction "7_7") (pintype "bidirectional"))
    )
    (net (code "48") (name "/SENSOR_LED1") (class "Default")
      (node (ref "R10") (pin "1") (pinfunction "1_1") (pintype "passive"))
      (node (ref "U$6") (pin "6") (pinfunction "6_6") (pintype "bidirectional"))
    )
    (net (code "49") (name "/SENSOR_LED2") (class "Default")
      (node (ref "R11") (pin "1") (pinfunction "1_1") (pintype "passive"))
      (node (ref "U$6") (pin "5") (pinfunction "5_5") (pintype "bidirectional"))
    )
    (net (code "50") (name "/SENSOR_LED3") (class "Default")
      (node (ref "R12") (pin "1") (pinfunction "1_1") (pintype "passive"))
      (node (ref "U$6") (pin "4") (pinfunction "4_4") (pintype "bidirectional"))
    )
    (net (code "51") (name "/SENSOR_PULL") (class "Default")
      (node (ref "R7") (pin "2") (pinfunction "2_2") (pintype "passive"))
      (node (ref "R8") (pin "2") (pinfunction "2_2") (pintype "passive"))
      (node (ref "R9") (pin "2") (pinfunction "2_2") (pintype "passive"))
      (node (ref "SJ7") (pin "1") (pinfunction "1_1") (pintype "passive"))
      (node (ref "SJ8") (pin "1") (pinfunction "1_1") (pintype "passive"))
    )
    (net (code "52") (name "/VALVE_+3V3") (class "Default")
      (node (ref "R3") (pin "1") (pinfunction "1_1") (pintype "passive"))
      (node (ref "R4") (pin "1") (pinfunction "1_1") (pintype "passive"))
      (node (ref "R5") (pin "1") (pinfunction "1_1") (pintype "passive"))
      (node (ref "R6") (pin "1") (pinfunction "1_1") (pintype "passive"))
      (node (ref "SENSOR5") (pin "2") (pinfunction "2_2") (pintype "bidirectional"))
      (node (ref "U$2") (pin "8") (pinfunction "8_8") (pintype "bidirectional"))
    )
    (net (code "53") (name "/VALVE_+5V") (class "Default")
      (node (ref "C1") (pin "1") (pinfunction "1_1") (pintype "passive"))
      (node (ref "C2") (pin "1") (pinfunction "1_1") (pintype "passive"))
      (node (ref "L9110") (pin "2") (pinfunction "VCC_2") (pintype "power_in"))
      (node (ref "L9110") (pin "3") (pinfunction "VCC_3") (pintype "power_in"))
      (node (ref "U$2") (pin "9") (pinfunction "9_9") (pintype "bidirectional"))
    )
    (net (code "54") (name "/VALVE_CLOSED") (class "Default")
      (node (ref "R3") (pin "2") (pinfunction "2_2") (pintype "passive"))
      (node (ref "U$2") (pin "2") (pinfunction "2_2") (pintype "bidirectional"))
      (node (ref "VALVE") (pin "4") (pinfunction "4_4") (pintype "bidirectional"))
    )
    (net (code "55") (name "/VALVE_CONTROL1") (class "Default")
      (node (ref "L9110") (pin "6") (pinfunction "IA_6") (pintype "input"))
      (node (ref "R6") (pin "2") (pinfunction "2_2") (pintype "passive"))
      (node (ref "U$2") (pin "6") (pinfunction "6_6") (pintype "bidirectional"))
    )
    (net (code "56") (name "/VALVE_CONTROL2") (class "Default")
      (node (ref "L9110") (pin "7") (pinfunction "IB_7") (pintype "input"))
      (node (ref "R5") (pin "2") (pinfunction "2_2") (pintype "passive"))
      (node (ref "U$2") (pin "5") (pinfunction "5_5") (pintype "bidirectional"))
    )
    (net (code "57") (name "/VALVE_GND") (class "Default")
      (node (ref "C1") (pin "2") (pinfunction "2_2") (pintype "passive"))
      (node (ref "C2") (pin "2") (pinfunction "2_2") (pintype "passive"))
      (node (ref "L9110") (pin "5") (pinfunction "GND_5") (pintype "power_in"))
      (node (ref "L9110") (pin "8") (pinfunction "GND_8") (pintype "power_in"))
      (node (ref "R1") (pin "2") (pinfunction "2_2") (pintype "passive"))
      (node (ref "R2") (pin "2") (pinfunction "2_2") (pintype "passive"))
      (node (ref "U$2") (pin "7") (pinfunction "7_7") (pintype "bidirectional"))
      (node (ref "VALVE") (pin "1") (pinfunction "1_1") (pintype "bidirectional"))
    )
    (net (code "58") (name "/VALVE_LED") (class "Default")
      (node (ref "U$2") (pin "4") (pinfunction "4_4") (pintype "bidirectional"))
      (node (ref "VLV_LED") (pin "1") (pinfunction "1_1") (pintype "bidirectional"))
    )
    (net (code "59") (name "/VALVE_OPENED") (class "Default")
      (node (ref "R4") (pin "2") (pinfunction "2_2") (pintype "passive"))
      (node (ref "U$2") (pin "3") (pinfunction "3_3") (pintype "bidirectional"))
      (node (ref "VALVE") (pin "5") (pinfunction "5_5") (pintype "bidirectional"))
    )
    (net (code "60") (name "/VALVE_SENSOR3") (class "Default")
      (node (ref "R1") (pin "1") (pinfunction "1_1") (pintype "passive"))
      (node (ref "SENSOR5") (pin "1") (pinfunction "1_1") (pintype "bidirectional"))
      (node (ref "U$2") (pin "1") (pinfunction "1_1") (pintype "bidirectional"))
    )
    (net (code "61") (name "Net-(D1-K)") (class "Default")
      (node (ref "D1") (pin "C") (pinfunction "K_C") (pintype "bidirectional"))
      (node (ref "OK1") (pin "1") (pinfunction "1_1") (pintype "passive"))
      (node (ref "R24") (pin "1") (pinfunction "1_1") (pintype "passive"))
    )
    (net (code "62") (name "Net-(D1-PadA)") (class "Default")
      (node (ref "D1") (pin "A") (pinfunction "A_A") (pintype "bidirectional"))
      (node (ref "OK1") (pin "2") (pinfunction "2_2") (pintype "passive"))
      (node (ref "PINP1") (pin "1") (pinfunction "1_1") (pintype "bidirectional"))
    )
    (net (code "63") (name "Net-(D2-K)") (class "Default")
      (node (ref "D2") (pin "C") (pinfunction "K_C") (pintype "bidirectional"))
      (node (ref "OK2") (pin "1") (pinfunction "1_1") (pintype "passive"))
      (node (ref "R23") (pin "1") (pinfunction "1_1") (pintype "passive"))
    )
    (net (code "64") (name "Net-(D2-PadA)") (class "Default")
      (node (ref "D2") (pin "A") (pinfunction "A_A") (pintype "bidirectional"))
      (node (ref "OK2") (pin "2") (pinfunction "2_2") (pintype "passive"))
      (node (ref "PINP2") (pin "1") (pinfunction "1_1") (pintype "bidirectional"))
    )
    (net (code "65") (name "Net-(D3-K)") (class "Default")
      (node (ref "D3") (pin "C") (pinfunction "K_C") (pintype "bidirectional"))
      (node (ref "OK3") (pin "1") (pinfunction "1_1") (pintype "passive"))
      (node (ref "R22") (pin "1") (pinfunction "1_1") (pintype "passive"))
    )
    (net (code "66") (name "Net-(D3-PadA)") (class "Default")
      (node (ref "D3") (pin "A") (pinfunction "A_A") (pintype "bidirectional"))
      (node (ref "OK3") (pin "2") (pinfunction "2_2") (pintype "passive"))
      (node (ref "PINP3") (pin "1") (pinfunction "1_1") (pintype "bidirectional"))
    )
    (net (code "67") (name "Net-(D4-PadA)") (class "Default")
      (node (ref "D4") (pin "A") (pinfunction "A_A") (pintype "passive"))
      (node (ref "R2_OC1") (pin "2") (pinfunction "2_2") (pintype "passive"))
    )
    (net (code "68") (name "Net-(D6-PadA)") (class "Default")
      (node (ref "D6") (pin "A") (pinfunction "A_A") (pintype "passive"))
      (node (ref "R3_OC") (pin "2") (pinfunction "2_2") (pintype "passive"))
    )
    (net (code "69") (name "Net-(L9110-OA)") (class "Default")
      (node (ref "C3") (pin "2") (pinfunction "2_2") (pintype "passive"))
      (node (ref "L9110") (pin "1") (pinfunction "OA_1") (pintype "output"))
      (node (ref "VALVE") (pin "2") (pinfunction "2_2") (pintype "bidirectional"))
    )
    (net (code "70") (name "Net-(L9110-OB)") (class "Default")
      (node (ref "C3") (pin "1") (pinfunction "1_1") (pintype "passive"))
      (node (ref "L9110") (pin "4") (pinfunction "OB_4") (pintype "output"))
      (node (ref "VALVE") (pin "3") (pinfunction "3_3") (pintype "bidirectional"))
    )
    (net (code "71") (name "Net-(PINP1-Pad2)") (class "Default")
      (node (ref "PINP1") (pin "2") (pinfunction "2_2") (pintype "bidirectional"))
      (node (ref "R24") (pin "2") (pinfunction "2_2") (pintype "passive"))
    )
    (net (code "72") (name "Net-(PINP2-Pad2)") (class "Default")
      (node (ref "PINP2") (pin "2") (pinfunction "2_2") (pintype "bidirectional"))
      (node (ref "R23") (pin "2") (pinfunction "2_2") (pintype "passive"))
    )
    (net (code "73") (name "Net-(PINP3-Pad2)") (class "Default")
      (node (ref "PINP3") (pin "2") (pinfunction "2_2") (pintype "bidirectional"))
      (node (ref "R22") (pin "2") (pinfunction "2_2") (pintype "passive"))
    )
    (net (code "74") (name "Net-(R2-Pad1)") (class "Default")
      (node (ref "R2") (pin "1") (pinfunction "1_1") (pintype "passive"))
      (node (ref "VLV_LED") (pin "2") (pinfunction "2_2") (pintype "bidirectional"))
    )
    (net (code "75") (name "Net-(R2_LED-Pad1)") (class "Default")
      (node (ref "R2_LED") (pin "1") (pinfunction "1_1") (pintype "bidirectional"))
      (node (ref "R34") (pin "1") (pinfunction "1_1") (pintype "passive"))
    )
    (net (code "76") (name "Net-(R2_OC1-EMIT)") (class "Default")
      (node (ref "R2_OC1") (pin "3") (pinfunction "EMIT_3") (pintype "passive"))
      (node (ref "R31") (pin "1") (pinfunction "1_1") (pintype "passive"))
    )
    (net (code "77") (name "Net-(R2_OC1-Pad1)") (class "Default")
      (node (ref "R2_OC1") (pin "1") (pinfunction "1_1") (pintype "passive"))
      (node (ref "R32") (pin "1") (pinfunction "1_1") (pintype "passive"))
    )
    (net (code "78") (name "Net-(R2_RELAY-COIL_B)") (class "Default")
      (node (ref "D5") (pin "A") (pinfunction "A_A") (pintype "passive"))
      (node (ref "R2_RELAY") (pin "2") (pinfunction "COIL_B_2") (pintype "bidirectional"))
      (node (ref "U$8") (pin "3") (pinfunction "COLLECTOR_3") (pintype "passive"))
    )
    (net (code "79") (name "Net-(R2_RELAY-COM)") (class "Default")
      (node (ref "R2_RELAY") (pin "3") (pinfunction "COM_3") (pintype "bidirectional"))
      (node (ref "U$10") (pin "1") (pinfunction "1_1") (pintype "bidirectional"))
      (node (ref "U$12") (pin "1") (pinfunction "1_1") (pintype "bidirectional"))
    )
    (net (code "80") (name "Net-(R2_RELAY-NC)") (class "Default")
      (node (ref "R2_RELAY") (pin "5") (pinfunction "NC_5") (pintype "bidirectional"))
      (node (ref "U$11") (pin "1") (pinfunction "1_1") (pintype "bidirectional"))
    )
    (net (code "81") (name "Net-(R2_RELAY-NO)") (class "Default")
      (node (ref "R2_RELAY") (pin "4") (pinfunction "NO_4") (pintype "bidirectional"))
      (node (ref "U$9") (pin "1") (pinfunction "1_1") (pintype "bidirectional"))
    )
    (net (code "82") (name "Net-(R3_OC-EMIT)") (class "Default")
      (node (ref "R37") (pin "1") (pinfunction "1_1") (pintype "passive"))
      (node (ref "R3_OC") (pin "3") (pinfunction "EMIT_3") (pintype "passive"))
    )
    (net (code "83") (name "Net-(R10-Pad2)") (class "Default")
      (node (ref "R10") (pin "2") (pinfunction "2_2") (pintype "passive"))
      (node (ref "SENLED1") (pin "1") (pinfunction "1_1") (pintype "bidirectional"))
    )
    (net (code "84") (name "Net-(R11-Pad2)") (class "Default")
      (node (ref "R11") (pin "2") (pinfunction "2_2") (pintype "passive"))
      (node (ref "SENLED2") (pin "1") (pinfunction "1_1") (pintype "bidirectional"))
    )
    (net (code "85") (name "Net-(R12-Pad2)") (class "Default")
      (node (ref "R12") (pin "2") (pinfunction "2_2") (pintype "passive"))
      (node (ref "SENLED3") (pin "1") (pinfunction "1_1") (pintype "bidirectional"))
    )
    (net (code "86") (name "Net-(R36-Pad1)") (class "Default")
      (node (ref "R36") (pin "1") (pinfunction "1_1") (pintype "passive"))
      (node (ref "R3_OC") (pin "1") (pinfunction "1_1") (pintype "passive"))
    )
    (net (code "87") (name "Net-(R38-Pad1)") (class "Default")
      (node (ref "R38") (pin "1") (pinfunction "1_1") (pintype "passive"))
      (node (ref "R3_LED") (pin "1") (pinfunction "1_1") (pintype "bidirectional"))
    )
    (net (code "88") (name "Net-(R39-Pad1)") (class "Default")
      (node (ref "R39") (pin "1") (pinfunction "1_1") (pintype "passive"))
      (node (ref "R3_LED1") (pin "1") (pinfunction "1_1") (pintype "bidirectional"))
    )
    (net (code "89") (name "Net-(SENSOR1-Pad2)") (class "Default")
      (node (ref "SENSOR1") (pin "2") (pinfunction "2_2") (pintype "bidirectional"))
      (node (ref "SJ1") (pin "1") (pinfunction "1_1") (pintype "passive"))
      (node (ref "SJ2") (pin "1") (pinfunction "1_1") (pintype "passive"))
    )
    (net (code "90") (name "Net-(SENSOR2-Pad2)") (class "Default")
      (node (ref "SENSOR2") (pin "2") (pinfunction "2_2") (pintype "bidirectional"))
      (node (ref "SJ3") (pin "1") (pinfunction "1_1") (pintype "passive"))
      (node (ref "SJ4") (pin "1") (pinfunction "1_1") (pintype "passive"))
    )
    (net (code "91") (name "Net-(SENSOR3-Pad2)") (class "Default")
      (node (ref "SENSOR3") (pin "2") (pinfunction "2_2") (pintype "bidirectional"))
      (node (ref "SJ5") (pin "1") (pinfunction "1_1") (pintype "passive"))
      (node (ref "SJ6") (pin "1") (pinfunction "1_1") (pintype "passive"))
    )
    (net (code "92") (name "Net-(U$8-BASE)") (class "Default")
      (node (ref "R31") (pin "2") (pinfunction "2_2") (pintype "passive"))
      (node (ref "U$8") (pin "1") (pinfunction "BASE_1") (pintype "passive"))
    )
    (net (code "93") (name "Net-(U$13-BASE)") (class "Default")
      (node (ref "R37") (pin "2") (pinfunction "2_2") (pintype "passive"))
      (node (ref "U$13") (pin "1") (pinfunction "BASE_1") (pintype "passive"))
    )
    (net (code "94") (name "Net-(U$13-COLLECTOR)") (class "Default")
      (node (ref "D7") (pin "A") (pinfunction "A_A") (pintype "passive"))
      (node (ref "U$13") (pin "3") (pinfunction "COLLECTOR_3") (pintype "passive"))
      (node (ref "U$3") (pin "9") (pinfunction "9_9") (pintype "bidirectional"))
    )
    (net (code "95") (name "Net-(U$15-Pad1)") (class "Default")
      (node (ref "U$15") (pin "1") (pinfunction "1_1") (pintype "bidirectional"))
      (node (ref "U$3") (pin "10") (pinfunction "10_10") (pintype "bidirectional"))
    )
    (net (code "96") (name "Net-(U$16-Pad1)") (class "Default")
      (node (ref "U$16") (pin "1") (pinfunction "1_1") (pintype "bidirectional"))
      (node (ref "U$3") (pin "5") (pinfunction "5_5") (pintype "bidirectional"))
    )
    (net (code "97") (name "Net-(U$17-Pad1)") (class "Default")
      (node (ref "U$17") (pin "1") (pinfunction "1_1") (pintype "bidirectional"))
      (node (ref "U$3") (pin "1") (pinfunction "1_1") (pintype "bidirectional"))
    )
    (net (code "98") (name "Net-(U2-BASE)") (class "Default")
      (node (ref "R30") (pin "2") (pinfunction "2_2") (pintype "passive"))
      (node (ref "U2") (pin "1") (pinfunction "BASE_1") (pintype "passive"))
    )
    (net (code "99") (name "Net-(U2-COLLECTOR)") (class "Default")
      (node (ref "RELAY4") (pin "1") (pinfunction "1_1") (pintype "bidirectional"))
      (node (ref "U2") (pin "3") (pinfunction "COLLECTOR_3") (pintype "passive"))
    )
    (net (code "100") (name "Net-(U2-EMITTER)") (class "Default")
      (node (ref "RELAY4") (pin "2") (pinfunction "2_2") (pintype "bidirectional"))
      (node (ref "U2") (pin "2") (pinfunction "EMITTER_2") (pintype "passive"))
    )
    (net (code "101") (name "Net-(U5-BASE)") (class "Default")
      (node (ref "R29") (pin "2") (pinfunction "2_2") (pintype "passive"))
      (node (ref "U5") (pin "1") (pinfunction "BASE_1") (pintype "passive"))
    )
    (net (code "102") (name "Net-(U5-COLLECTOR)") (class "Default")
      (node (ref "RELAY5") (pin "1") (pinfunction "1_1") (pintype "bidirectional"))
      (node (ref "U5") (pin "3") (pinfunction "COLLECTOR_3") (pintype "passive"))
    )
    (net (code "103") (name "Net-(U5-EMITTER)") (class "Default")
      (node (ref "RELAY5") (pin "2") (pinfunction "2_2") (pintype "bidirectional"))
      (node (ref "U5") (pin "2") (pinfunction "EMITTER_2") (pintype "passive"))
    )
    (net (code "104") (name "Net-(U6-BASE)") (class "Default")
      (node (ref "R28") (pin "2") (pinfunction "2_2") (pintype "passive"))
      (node (ref "U6") (pin "1") (pinfunction "BASE_1") (pintype "passive"))
    )
    (net (code "105") (name "Net-(U6-COLLECTOR)") (class "Default")
      (node (ref "RELAY6") (pin "1") (pinfunction "1_1") (pintype "bidirectional"))
      (node (ref "U6") (pin "3") (pinfunction "COLLECTOR_3") (pintype "passive"))
    )
    (net (code "106") (name "Net-(U6-EMITTER)") (class "Default")
      (node (ref "RELAY6") (pin "2") (pinfunction "2_2") (pintype "bidirectional"))
      (node (ref "U6") (pin "2") (pinfunction "EMITTER_2") (pintype "passive"))
    )
    (net (code "107") (name "unconnected-(U$1-Pad9)") (class "Default")
      (node (ref "U$1") (pin "9") (pinfunction "9_9") (pintype "bidirectional"))
    )
    (net (code "108") (name "unconnected-(U$3-Pad6)") (class "Default")
      (node (ref "U$3") (pin "6") (pinfunction "6_6") (pintype "bidirectional"))
    )
    (net (code "109") (name "unconnected-(U$4-Pad1)") (class "Default")
      (node (ref "U$4") (pin "1") (pinfunction "1_1") (pintype "bidirectional"))
    )
    (net (code "110") (name "unconnected-(U$4-Pad2)") (class "Default")
      (node (ref "U$4") (pin "2") (pinfunction "2_2") (pintype "bidirectional"))
    )
    (net (code "111") (name "unconnected-(U$7-Pad1)") (class "Default")
      (node (ref "U$7") (pin "1") (pinfunction "1_1") (pintype "bidirectional"))
    )
    (net (code "112") (name "unconnected-(U$7-Pad4)") (class "Default")
      (node (ref "U$7") (pin "4") (pinfunction "4_4") (pintype "bidirectional"))
    )
    (net (code "113") (name "unconnected-(U$18-Pad9)") (class "Default")
      (node (ref "U$18") (pin "9") (pinfunction "9_9") (pintype "bidirectional"))
    )
  )
)
